# partybooth.net
KiCad netlist of a schematic drawn in EAGLE
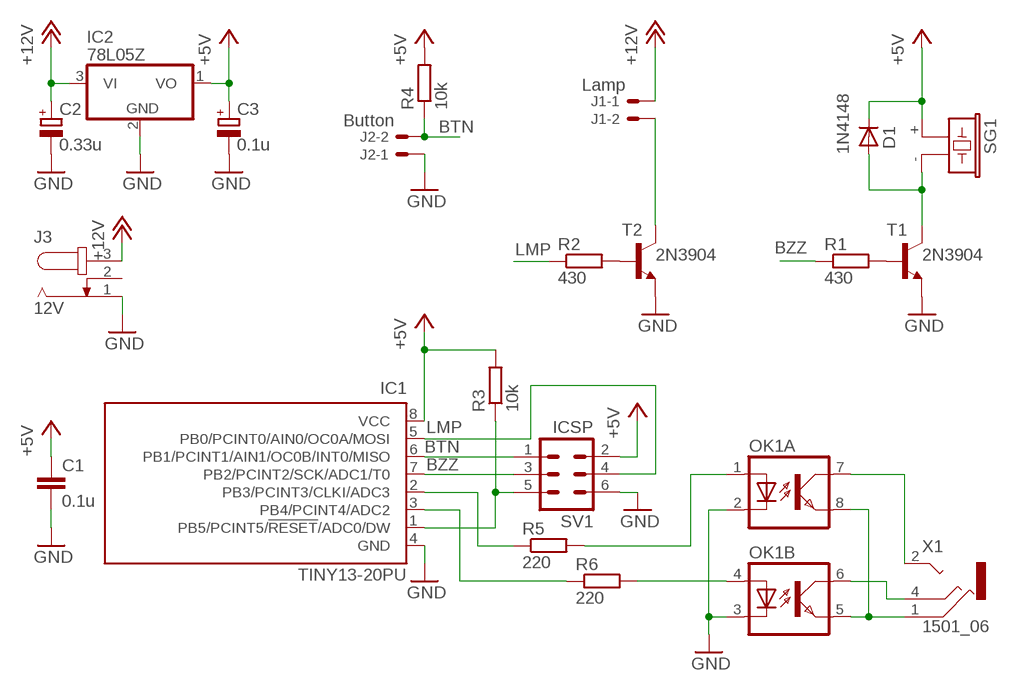
[diagram p0: schematic, sheet 1]

(export (version "E")
  (design (tool "Eeschema 10.0.6"))
  (components
    (comp (ref "C1")
      (value "0.1u")
      (footprint "eagle-import:C050-025X075")
      (libsource (lib "eagle-import") (part "C-EU050-025X075"))
    )
    (comp (ref "C2")
      (value "0.33u")
      (footprint "eagle-import:E5-6")
      (libsource (lib "eagle-import") (part "CPOL-EUE5-6"))
    )
    (comp (ref "C3")
      (value "0.1u")
      (footprint "eagle-import:E5-5")
      (libsource (lib "eagle-import") (part "CPOL-EUE5-5"))
    )
    (comp (ref "D1")
      (value "1N4148")
      (footprint "eagle-import:DO35-7")
      (libsource (lib "eagle-import") (part "1N4148DO35-7"))
    )
    (comp (ref "IC1")
      (value "TINY13-20PU")
      (footprint "eagle-import:DIL08")
      (fields (field (name "MPN") "ATTINY13-20PU"))
      (libsource (lib "eagle-import") (part "TINY13PU-20"))
    )
    (comp (ref "IC2")
      (value "78L05Z")
      (footprint "eagle-import:TO92")
      (libsource (lib "eagle-import") (part "78ZL05"))
    )
    (comp (ref "J1")
      (value "Lamp")
      (footprint "eagle-import:6410-02")
      (libsource (lib "eagle-import") (part "22-?-0227-2021"))
    )
    (comp (ref "J2")
      (value "Button")
      (footprint "eagle-import:6410-02")
      (libsource (lib "eagle-import") (part "22-?-0227-2021"))
    )
    (comp (ref "J3")
      (value "12V")
      (footprint "eagle-import:SPC4077")
      (libsource (lib "eagle-import") (part "JACK-PLUG0"))
    )
    (comp (ref "OK1")
      (value "ILD2")
      (footprint "eagle-import:DIL08")
      (libsource (lib "eagle-import") (part "ILD2"))
    )
    (comp (ref "R1")
      (value "430")
      (footprint "eagle-import:0204_7")
      (libsource (lib "eagle-import") (part "R-EU_0204/7"))
    )
    (comp (ref "R2")
      (value "430")
      (footprint "eagle-import:0204_7")
      (libsource (lib "eagle-import") (part "R-EU_0204/7"))
    )
    (comp (ref "R3")
      (value "10k")
      (footprint "eagle-import:0204_7")
      (libsource (lib "eagle-import") (part "R-EU_0204/7"))
    )
    (comp (ref "R4")
      (value "10k")
      (footprint "eagle-import:0204_7")
      (libsource (lib "eagle-import") (part "R-EU_0204/7"))
    )
    (comp (ref "R5")
      (value "220")
      (footprint "eagle-import:0204_7")
      (libsource (lib "eagle-import") (part "R-EU_0204/7"))
    )
    (comp (ref "R6")
      (value "220")
      (footprint "eagle-import:0204_7")
      (libsource (lib "eagle-import") (part "R-EU_0204/7"))
    )
    (comp (ref "SG1")
      (value "F/CM12P")
      (footprint "eagle-import:F_CM12P")
      (libsource (lib "eagle-import") (part "F/CM12P"))
    )
    (comp (ref "SV1")
      (value "ICSP")
      (footprint "eagle-import:MA03-2")
      (libsource (lib "eagle-import") (part "MA03-2"))
    )
    (comp (ref "T1")
      (value "2N3904")
      (footprint "eagle-import:TO92")
      (libsource (lib "eagle-import") (part "2N3904"))
    )
    (comp (ref "T2")
      (value "2N3904")
      (footprint "eagle-import:TO92")
      (libsource (lib "eagle-import") (part "2N3904"))
    )
    (comp (ref "X1")
      (value "1501_06")
      (footprint "eagle-import:1501_06")
      (libsource (lib "eagle-import") (part "1501_06"))
    )
  )
  (nets
    (net (code "1") (name "+5V") (class "Default")
      (node (ref "C1") (pin "1") (pinfunction "1_1") (pintype "passive"))
      (node (ref "C3") (pin "+") (pinfunction "+_+") (pintype "passive"))
      (node (ref "D1") (pin "C") (pinfunction "C_C") (pintype "passive"))
      (node (ref "IC1") (pin "8") (pinfunction "VCC_8") (pintype "power_in"))
      (node (ref "IC2") (pin "1") (pinfunction "VO_1") (pintype "passive"))
      (node (ref "R3") (pin "2") (pinfunction "2_2") (pintype "passive"))
      (node (ref "R4") (pin "2") (pinfunction "2_2") (pintype "passive"))
      (node (ref "SG1") (pin "+") (pinfunction "1_+") (pintype "passive"))
      (node (ref "SV1") (pin "2") (pinfunction "2_2") (pintype "passive"))
    )
    (net (code "2") (name "+12V") (class "Default")
      (node (ref "C2") (pin "+") (pinfunction "+_+") (pintype "passive"))
      (node (ref "IC2") (pin "3") (pinfunction "VI_3") (pintype "input"))
      (node (ref "J1") (pin "1") (pinfunction "S_1") (pintype "passive"))
      (node (ref "J3") (pin "3") (pinfunction "3_3") (pintype "passive"))
    )
    (net (code "3") (name "/BTN") (class "Default")
      (node (ref "IC1") (pin "6") (pinfunction "PB1/PCINT1/AIN1/OC0B/INT0/MISO_6") (pintype "bidirectional"))
      (node (ref "J2") (pin "2") (pinfunction "S_2") (pintype "passive"))
      (node (ref "R4") (pin "1") (pinfunction "1_1") (pintype "passive"))
      (node (ref "SV1") (pin "1") (pinfunction "1_1") (pintype "passive"))
    )
    (net (code "4") (name "/BZZ") (class "Default")
      (node (ref "IC1") (pin "7") (pinfunction "PB2/PCINT2/SCK/ADC1/T0_7") (pintype "bidirectional"))
      (node (ref "R1") (pin "1") (pinfunction "1_1") (pintype "passive"))
      (node (ref "SV1") (pin "3") (pinfunction "3_3") (pintype "passive"))
    )
    (net (code "5") (name "/LMP") (class "Default")
      (node (ref "IC1") (pin "5") (pinfunction "PB0/PCINT0/AIN0/OC0A/MOSI_5") (pintype "bidirectional"))
      (node (ref "R2") (pin "1") (pinfunction "1_1") (pintype "passive"))
      (node (ref "SV1") (pin "4") (pinfunction "4_4") (pintype "passive"))
    )
    (net (code "6") (name "GND") (class "Default")
      (node (ref "C1") (pin "2") (pinfunction "2_2") (pintype "passive"))
      (node (ref "C2") (pin "-") (pinfunction "-_-") (pintype "passive"))
      (node (ref "C3") (pin "-") (pinfunction "-_-") (pintype "passive"))
      (node (ref "IC1") (pin "4") (pinfunction "GND_4") (pintype "power_in"))
      (node (ref "IC2") (pin "2") (pinfunction "GND_2") (pintype "passive"))
      (node (ref "J2") (pin "1") (pinfunction "S_1") (pintype "passive"))
      (node (ref "J3") (pin "1") (pinfunction "1_1") (pintype "passive"))
      (node (ref "OK1") (pin "2") (pinfunction "C_2") (pintype "passive"))
      (node (ref "OK1") (pin "3") (pinfunction "C_3") (pintype "passive"))
      (node (ref "SV1") (pin "6") (pinfunction "6_6") (pintype "passive"))
      (node (ref "T1") (pin "3") (pinfunction "E_3") (pintype "passive"))
      (node (ref "T2") (pin "3") (pinfunction "E_3") (pintype "passive"))
    )
    (net (code "7") (name "Net-(IC1-PB3{slash}PCINT3{slash}CLKI{slash}ADC3)") (class "Default")
      (node (ref "IC1") (pin "2") (pinfunction "PB3/PCINT3/CLKI/ADC3_2") (pintype "bidirectional"))
      (node (ref "R5") (pin "1") (pinfunction "1_1") (pintype "passive"))
    )
    (net (code "8") (name "Net-(IC1-PB4{slash}PCINT4{slash}ADC2)") (class "Default")
      (node (ref "IC1") (pin "3") (pinfunction "PB4/PCINT4/ADC2_3") (pintype "bidirectional"))
      (node (ref "R6") (pin "1") (pinfunction "1_1") (pintype "passive"))
    )
    (net (code "9") (name "Net-(IC1-PB5{slash}PCINT5{slash}~{RESET}{slash}ADC0{slash}DW)") (class "Default")
      (node (ref "IC1") (pin "1") (pinfunction "PB5/PCINT5/~{RESET}/ADC0/DW_1") (pintype "bidirectional"))
      (node (ref "R3") (pin "1") (pinfunction "1_1") (pintype "passive"))
      (node (ref "SV1") (pin "5") (pinfunction "5_5") (pintype "passive"))
    )
    (net (code "10") (name "Net-(J1B-S)") (class "Default")
      (node (ref "J1") (pin "2") (pinfunction "S_2") (pintype "passive"))
      (node (ref "T2") (pin "1") (pinfunction "C_1") (pintype "passive"))
    )
    (net (code "11") (name "Net-(OK1A-A)") (class "Default")
      (node (ref "OK1") (pin "1") (pinfunction "A_1") (pintype "passive"))
      (node (ref "R5") (pin "2") (pinfunction "2_2") (pintype "passive"))
    )
    (net (code "12") (name "Net-(OK1A-COL)") (class "Default")
      (node (ref "OK1") (pin "7") (pinfunction "COL_7") (pintype "passive"))
      (node (ref "X1") (pin "2") (pinfunction "2_2") (pintype "passive"))
    )
    (net (code "13") (name "Net-(OK1A-EMIT)") (class "Default")
      (node (ref "OK1") (pin "5") (pinfunction "EMIT_5") (pintype "passive"))
      (node (ref "OK1") (pin "8") (pinfunction "EMIT_8") (pintype "passive"))
      (node (ref "X1") (pin "1") (pinfunction "1_1") (pintype "passive"))
    )
    (net (code "14") (name "Net-(OK1B-A)") (class "Default")
      (node (ref "OK1") (pin "4") (pinfunction "A_4") (pintype "passive"))
      (node (ref "R6") (pin "2") (pinfunction "2_2") (pintype "passive"))
    )
    (net (code "15") (name "Net-(OK1B-COL)") (class "Default")
      (node (ref "OK1") (pin "6") (pinfunction "COL_6") (pintype "passive"))
      (node (ref "X1") (pin "4") (pinfunction "3_4") (pintype "passive"))
    )
    (net (code "16") (name "Net-(SG1-2)") (class "Default")
      (node (ref "D1") (pin "A") (pinfunction "A_A") (pintype "passive"))
      (node (ref "SG1") (pin "-") (pinfunction "2_-") (pintype "passive"))
      (node (ref "T1") (pin "1") (pinfunction "C_1") (pintype "passive"))
    )
    (net (code "17") (name "Net-(T1-B)") (class "Default")
      (node (ref "R1") (pin "2") (pinfunction "2_2") (pintype "passive"))
      (node (ref "T1") (pin "2") (pinfunction "B_2") (pintype "passive"))
    )
    (net (code "18") (name "Net-(T2-B)") (class "Default")
      (node (ref "R2") (pin "2") (pinfunction "2_2") (pintype "passive"))
      (node (ref "T2") (pin "2") (pinfunction "B_2") (pintype "passive"))
    )
    (net (code "19") (name "unconnected-(J3-Pad2)") (class "Default")
      (node (ref "J3") (pin "2") (pinfunction "2_2") (pintype "passive"))
    )
  )
)
